# Power.net
KiCad netlist of a schematic drawn in Altium Designer
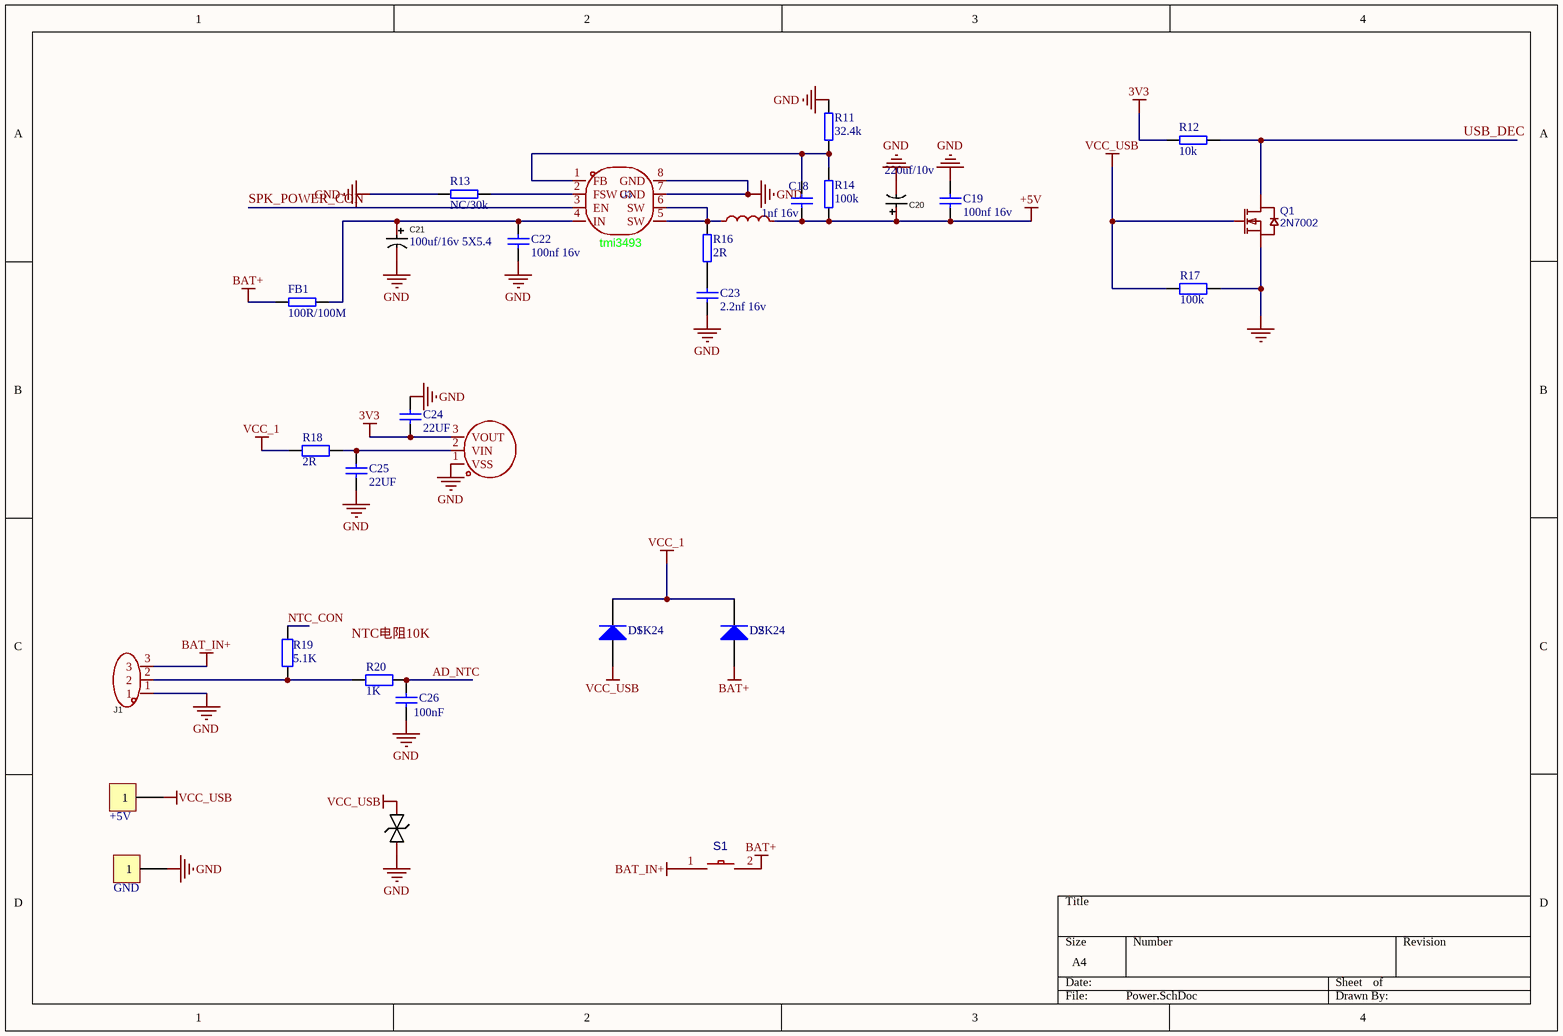
[diagram p0: Power.SchDoc]

(export (version "E")
  (design (tool "Eeschema 10.0.6"))
  (components
    (comp (ref "C18")
      (value "1nf 16v")
      (footprint "0603_C")
      (description "Capacitor")
      (fields (field (name "PUBLISHER") "Altium Limited"))
      (libsource (lib "*") (part "Cap"))
    )
    (comp (ref "C19")
      (value "100nf 16v")
      (footprint "0603_C")
      (description "Capacitor")
      (fields (field (name "PUBLISHER") "Altium Limited"))
      (libsource (lib "*") (part "Cap"))
    )
    (comp (ref "C20")
      (value "220uf/10v")
      (footprint "SMD 6.3*7.7")
      (fields (field (name "MANUFACTURER PART") "RVT1A221M0605"))
      (libsource (lib "altium-import") (part "root_2_RVT1A221M0605_C72494_"))
    )
    (comp (ref "C21")
      (value "100uf/16v 5X5.4")
      (footprint "CAP-SMD_5*5.4")
      (fields (field (name "MANUFACTURER PART") "RVT1A221M0605"))
      (libsource (lib "altium-import") (part "root_0_RVT1A221M0605_C72494_"))
    )
    (comp (ref "C22")
      (value "100nf 16v")
      (footprint "0603_C")
      (description "Capacitor")
      (fields (field (name "PUBLISHER") "Altium Limited"))
      (libsource (lib "*") (part "Cap"))
    )
    (comp (ref "C23")
      (value "2.2nf 16v")
      (footprint "0603_C")
      (description "Capacitor")
      (fields (field (name "PUBLISHER") "Altium Limited"))
      (libsource (lib "*") (part "Cap"))
    )
    (comp (ref "C24") (value "22UF") (footprint "0805_C") (libsource (lib "DIY") (part "CAP")))
    (comp (ref "C25") (value "22UF") (footprint "0805_C") (libsource (lib "DIY") (part "CAP")))
    (comp (ref "C26") (value "100nF") (footprint "0603_C") (libsource (lib "DIY") (part "CAP")))
    (comp (ref "D1")
      (value "DSK24")
      (footprint "SOD-123FL")
      (description "High Conductance Fast Diode")
      (fields (field (name "PUBLISHER") "Altium Limited"))
      (libsource (lib "Miscellaneous Devices") (part "Diode 1N4148"))
    )
    (comp (ref "D2")
      (value "DSK24")
      (footprint "SOD-123FL")
      (description "High Conductance Fast Diode")
      (fields (field (name "PUBLISHER") "Altium Limited"))
      (libsource (lib "Miscellaneous Devices") (part "Diode 1N4148"))
    )
    (comp (ref "D3")
      (value "SMF6.0CA")
      (footprint "SOD-123 双向")
      (fields (field (name "MANUFACTURER PART") "SMF5.0CA"))
      (libsource (lib "altium-import") (part "root_1_SMF5.0CA_C726939_"))
    )
    (comp (ref "FB1") (value "100R/100M") (footprint "0805_R") (libsource (lib "DIY") (part "RES")))
    (comp (ref "J1")
      (value "3.96-3P LT")
      (footprint "CONN-SMD_3.96-3P-LT")
      (fields (field (name "MANUFACTURER PART") "BX-PH2.0-3PZZ"))
      (libsource (lib "altium-import") (part "root_2_BX-PH2.0-3PZZ_"))
    )
    (comp (ref "L3")
      (value "33uh 0650")
      (footprint "IND-SMD_L7.7-W6.6_APS0650")
      (fields (field (name "MANUFACTURERPART") "YSPI0518S-100M"))
      (libsource (lib "altium-import") (part "root_0_yspi0518s-100m_"))
    )
    (comp (ref "P1") (value "+5V") (footprint "PAD2") (libsource (lib "zzh-sch") (part "CON1")))
    (comp (ref "P2") (value "GND") (footprint "PAD2") (libsource (lib "zzh-sch") (part "CON1")))
    (comp (ref "Q1")
      (value "2N7002")
      (footprint "SOT-23")
      (fields
        (field (name "BOM_SUPPLIER PART") "C2890442")
        (field (name "BOM_MANUFACTURER PART") "JMTL3400A")
        (field (name "CONTRIBUTOR") "LCSC")
      )
      (libsource (lib "altium-import") (part "root_0_JMTL3400A_"))
    )
    (comp (ref "R11") (value "32.4k") (footprint "0603_R") (libsource (lib "DIY") (part "RES")))
    (comp (ref "R12") (value "10k") (footprint "0603_R") (libsource (lib "DIY") (part "RES")))
    (comp (ref "R13") (value "NC/30k") (footprint "0603_R") (libsource (lib "DIY") (part "RES")))
    (comp (ref "R14") (value "100k") (footprint "0603_R") (libsource (lib "DIY") (part "RES")))
    (comp (ref "R16") (value "2R") (footprint "0603_R") (libsource (lib "DIY") (part "RES")))
    (comp (ref "R17")
      (value "100k")
      (footprint "0603_r")
      (description "贴片电阻")
      (libsource (lib "") (part "Res1_1"))
    )
    (comp (ref "R18")
      (value "2R")
      (footprint "0805_R")
      (description "贴片电阻")
      (libsource (lib "电容电阻电感保险") (part "Res1"))
    )
    (comp (ref "R19")
      (value "5.1K")
      (footprint "0603_R")
      (description "贴片电阻")
      (libsource (lib "") (part "Res1_2"))
    )
    (comp (ref "R20")
      (value "1K")
      (footprint "0603_R")
      (description "贴片电阻")
      (libsource (lib "电容电阻电感保险") (part "Res1"))
    )
    (comp (ref "S1")
      (value "*")
      (footprint "大按键")
      (libsource (lib "altium-import") (part "root_0_TS-3625SP-2P_"))
    )
    (comp (ref "U3")
      (value "tmi3493")
      (footprint "SOP8")
      (fields (field (name "MANUFACTURERPART") "TMI3493"))
      (libsource (lib "altium-import") (part "root_0_tmi3493_"))
    )
    (comp (ref "U4")
      (value "HT7333-1-MS")
      (footprint "SOT-89")
      (fields (field (name "MANUFACTURERPART") "ME6210A30PG"))
      (libsource (lib "altium-import") (part "root_2_mirrored_me6210a30pg_"))
    )
  )
  (nets
    (net (code "1") (name "+5V") (class "Default")
      (node (ref "C18") (pin "1") (pinfunction "1_1") (pintype "passive"))
      (node (ref "C19") (pin "1") (pinfunction "1_1") (pintype "passive"))
      (node (ref "C20") (pin "1") (pinfunction "1_1") (pintype "passive"))
      (node (ref "L3") (pin "2") (pinfunction "2_2") (pintype "passive"))
      (node (ref "R14") (pin "2") (pinfunction "2_2") (pintype "passive"))
    )
    (net (code "2") (name "/AD_NTC") (class "Default")
      (node (ref "C26") (pin "2") (pintype "passive"))
      (node (ref "R20") (pin "2") (pinfunction "2_2") (pintype "passive"))
    )
    (net (code "3") (name "/NTC_CON") (class "Default")
      (node (ref "R19") (pin "1") (pinfunction "1_1") (pintype "passive"))
    )
    (net (code "5") (name "/SPK_POWER_CON") (class "Default")
      (node (ref "U3") (pin "3") (pinfunction "EN_3") (pintype "passive"))
    )
    (net (code "6") (name "/USB_DEC") (class "Default")
      (node (ref "Q1") (pin "3") (pinfunction "D_3") (pintype "passive"))
      (node (ref "R12") (pin "2") (pinfunction "2_2") (pintype "passive"))
    )
    (net (code "7") (name "3V3") (class "Default")
      (node (ref "C24") (pin "1") (pintype "passive"))
      (node (ref "R12") (pin "1") (pinfunction "1_1") (pintype "passive"))
      (node (ref "U4") (pin "3") (pinfunction "VOUT_3") (pintype "passive"))
    )
    (net (code "8") (name "BAT+") (class "Default")
      (node (ref "D2") (pin "1") (pinfunction "A_1") (pintype "passive"))
      (node (ref "FB1") (pin "2") (pinfunction "2_2") (pintype "passive"))
      (node (ref "S1") (pin "2") (pinfunction "2_2") (pintype "passive"))
    )
    (net (code "9") (name "BAT_IN+") (class "Default")
      (node (ref "J1") (pin "3") (pinfunction "3_3") (pintype "passive"))
      (node (ref "S1") (pin "1") (pinfunction "1_1") (pintype "passive"))
    )
    (net (code "10") (name "GND") (class "Default")
      (node (ref "C19") (pin "2") (pinfunction "2_2") (pintype "passive"))
      (node (ref "C20") (pin "2") (pinfunction "2_2") (pintype "passive"))
      (node (ref "C21") (pin "2") (pinfunction "2_2") (pintype "passive"))
      (node (ref "C22") (pin "2") (pinfunction "2_2") (pintype "passive"))
      (node (ref "C23") (pin "2") (pinfunction "2_2") (pintype "passive"))
      (node (ref "C24") (pin "2") (pintype "passive"))
      (node (ref "C25") (pin "1") (pintype "passive"))
      (node (ref "C26") (pin "1") (pintype "passive"))
      (node (ref "D3") (pin "1") (pinfunction "1_1") (pintype "passive"))
      (node (ref "J1") (pin "1") (pinfunction "1_1") (pintype "passive"))
      (node (ref "P2") (pin "1") (pinfunction "1_1") (pintype "passive"))
      (node (ref "Q1") (pin "2") (pinfunction "S_2") (pintype "passive"))
      (node (ref "R11") (pin "1") (pinfunction "1_1") (pintype "passive"))
      (node (ref "R13") (pin "2") (pinfunction "2_2") (pintype "passive"))
      (node (ref "R17") (pin "1") (pinfunction "1_1") (pintype "passive"))
      (node (ref "U3") (pin "7") (pinfunction "GND_7") (pintype "passive"))
      (node (ref "U3") (pin "8") (pinfunction "GND_8") (pintype "passive"))
      (node (ref "U4") (pin "1") (pinfunction "VSS_1") (pintype "passive"))
    )
    (net (code "11") (name "Net-(C23-Pad1)") (class "Default")
      (node (ref "C23") (pin "1") (pinfunction "1_1") (pintype "passive"))
      (node (ref "R16") (pin "2") (pinfunction "2_2") (pintype "passive"))
    )
    (net (code "12") (name "Net-(J1-Pad2)") (class "Default")
      (node (ref "J1") (pin "2") (pinfunction "2_2") (pintype "passive"))
      (node (ref "R19") (pin "2") (pinfunction "2_2") (pintype "passive"))
      (node (ref "R20") (pin "1") (pinfunction "1_1") (pintype "passive"))
    )
    (net (code "13") (name "Net-(L3-Pad1)") (class "Default")
      (node (ref "L3") (pin "1") (pinfunction "1_1") (pintype "passive"))
      (node (ref "R16") (pin "1") (pinfunction "1_1") (pintype "passive"))
      (node (ref "U3") (pin "5") (pinfunction "SW_5") (pintype "passive"))
      (node (ref "U3") (pin "6") (pinfunction "SW_6") (pintype "passive"))
    )
    (net (code "14") (name "Net-(U3-FB)") (class "Default")
      (node (ref "C18") (pin "2") (pinfunction "2_2") (pintype "passive"))
      (node (ref "R11") (pin "2") (pinfunction "2_2") (pintype "passive"))
      (node (ref "R14") (pin "1") (pinfunction "1_1") (pintype "passive"))
      (node (ref "U3") (pin "1") (pinfunction "FB_1") (pintype "passive"))
    )
    (net (code "15") (name "Net-(U3-FSW)") (class "Default")
      (node (ref "R13") (pin "1") (pinfunction "1_1") (pintype "passive"))
      (node (ref "U3") (pin "2") (pinfunction "FSW_2") (pintype "passive"))
    )
    (net (code "16") (name "Net-(U3-IN)") (class "Default")
      (node (ref "C21") (pin "1") (pinfunction "1_1") (pintype "passive"))
      (node (ref "C22") (pin "1") (pinfunction "1_1") (pintype "passive"))
      (node (ref "FB1") (pin "1") (pinfunction "1_1") (pintype "passive"))
      (node (ref "U3") (pin "4") (pinfunction "IN_4") (pintype "passive"))
    )
    (net (code "17") (name "Net-(U4-VIN)") (class "Default")
      (node (ref "C25") (pin "2") (pintype "passive"))
      (node (ref "R18") (pin "2") (pinfunction "2_2") (pintype "passive"))
      (node (ref "U4") (pin "2") (pinfunction "VIN_2") (pintype "passive"))
    )
    (net (code "18") (name "VCC_1") (class "Default")
      (node (ref "D1") (pin "2") (pinfunction "K_2") (pintype "passive"))
      (node (ref "D2") (pin "2") (pinfunction "K_2") (pintype "passive"))
      (node (ref "R18") (pin "1") (pinfunction "1_1") (pintype "passive"))
    )
    (net (code "19") (name "VCC_USB") (class "Default")
      (node (ref "D1") (pin "1") (pinfunction "A_1") (pintype "passive"))
      (node (ref "D3") (pin "2") (pinfunction "2_2") (pintype "passive"))
      (node (ref "P1") (pin "1") (pinfunction "1_1") (pintype "passive"))
      (node (ref "Q1") (pin "1") (pinfunction "G_1") (pintype "passive"))
      (node (ref "R17") (pin "2") (pinfunction "2_2") (pintype "passive"))
    )
  )
)
